# Power.net
KiCad netlist of a schematic drawn in Altium Designer
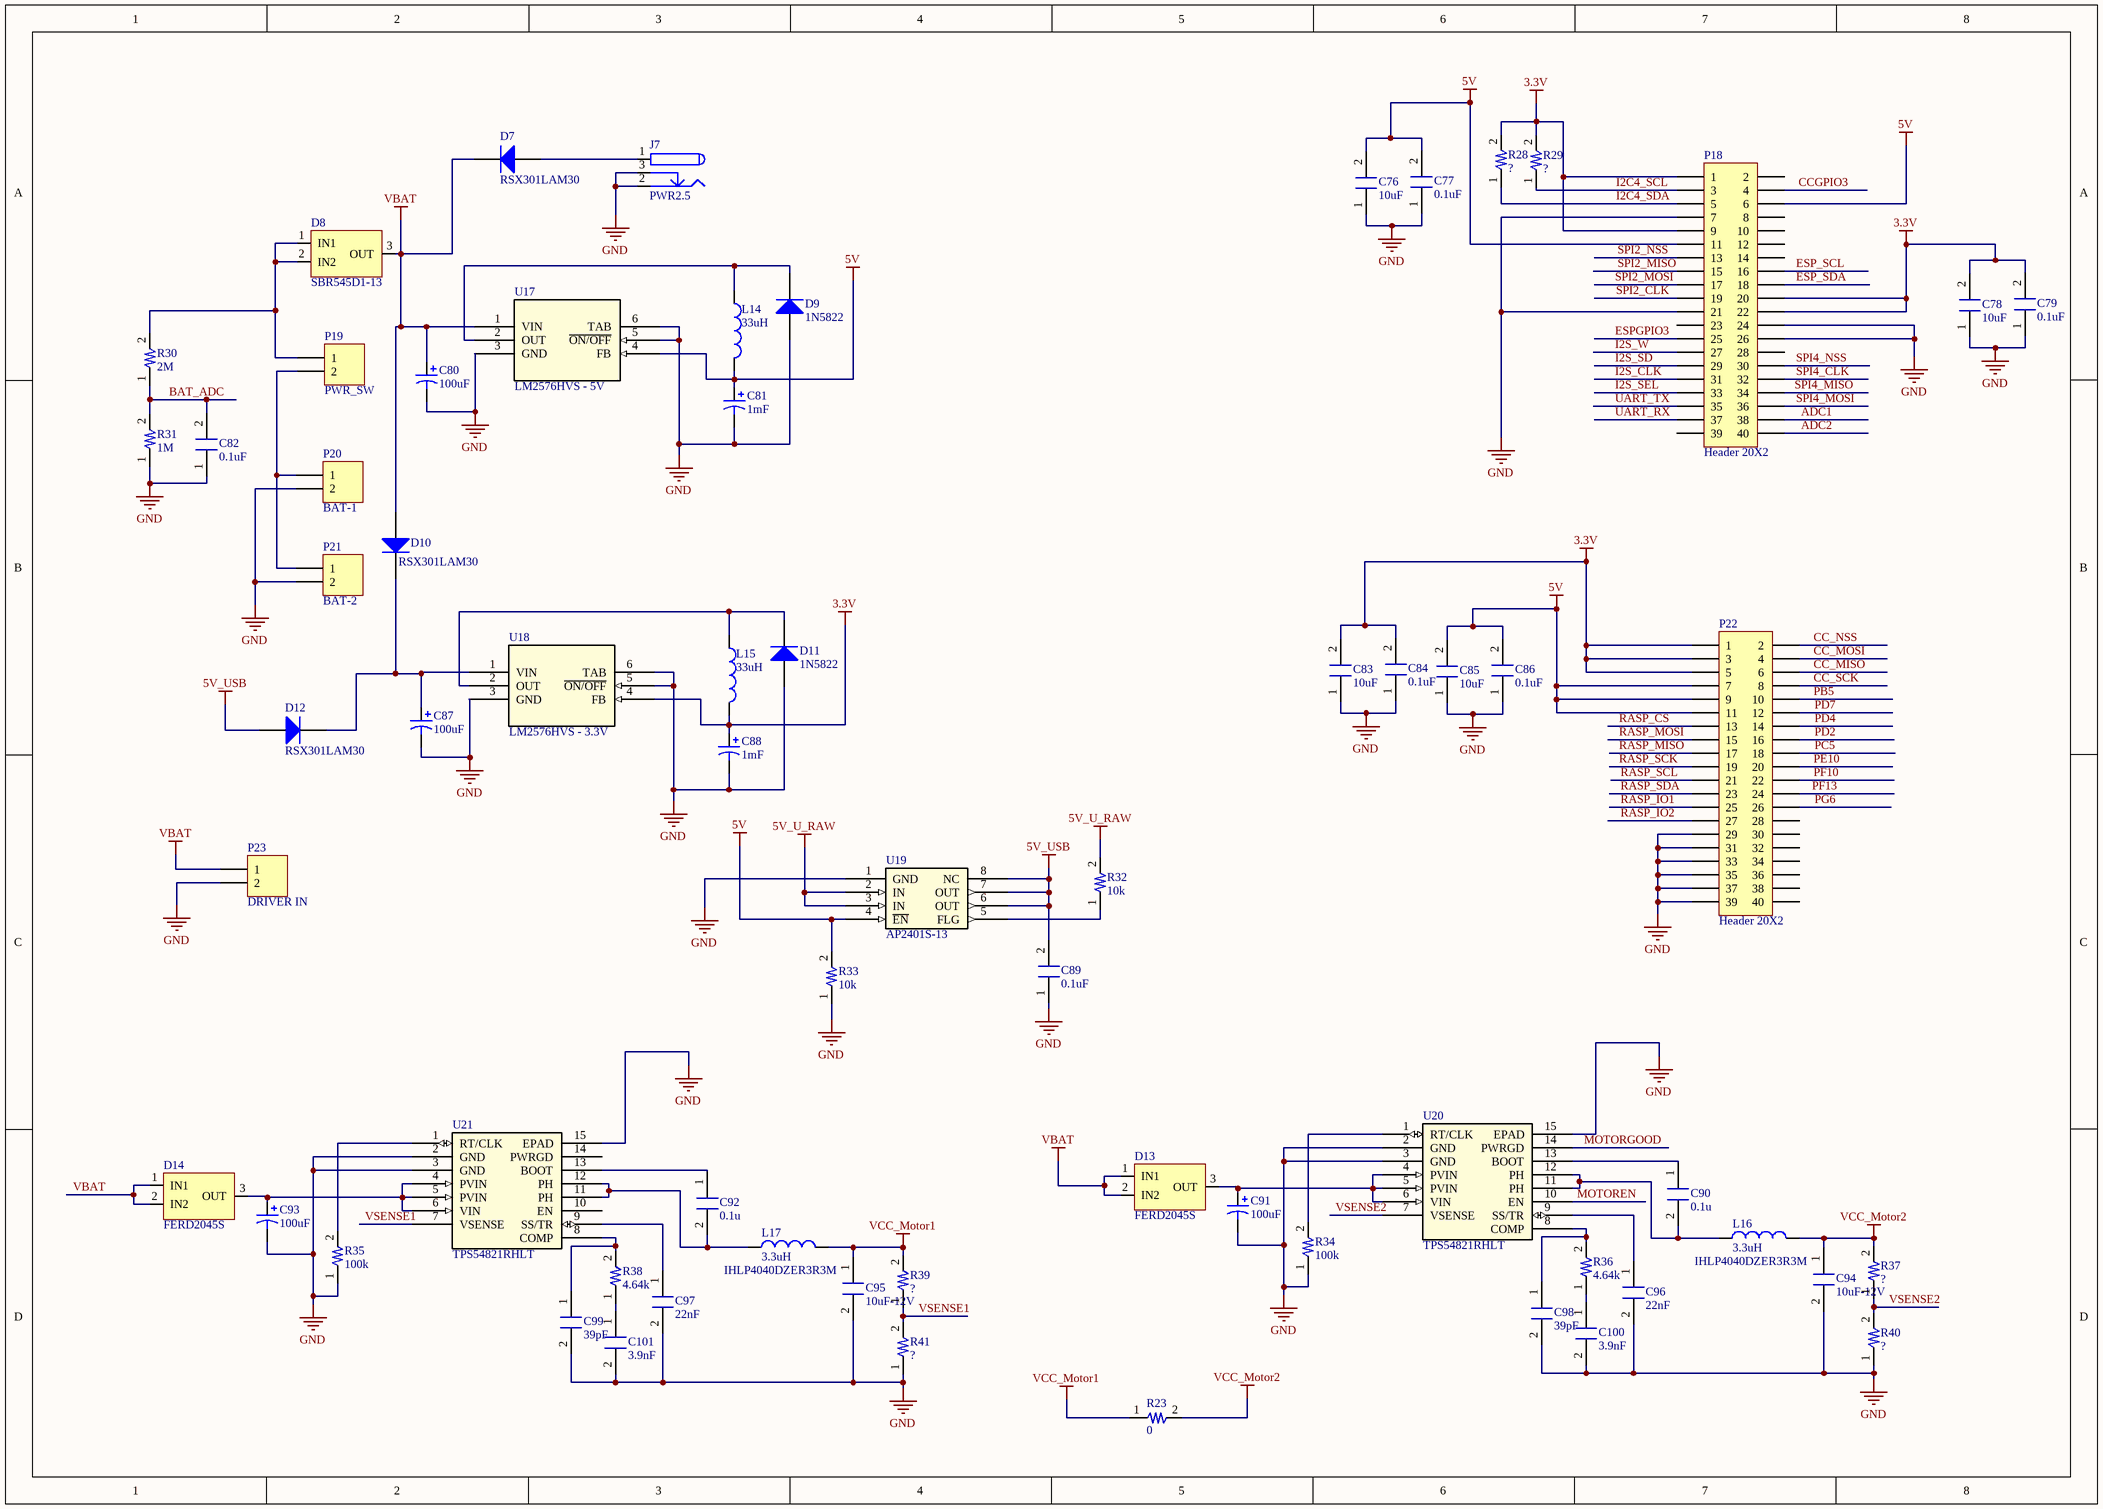
[diagram p0: Power.SchDoc]

(export (version "E")
  (design (tool "Eeschema 10.0.6"))
  (components
    (comp (ref "C76")
      (value "10uF")
      (footprint "Capacitor 0603")
      (fields (field (name "Comment") "Ceramic Capacitor"))
      (libsource (lib "Custom") (part "Ceramic Capacitor"))
    )
    (comp (ref "C77")
      (value "0.1uF")
      (footprint "Capacitor 0402")
      (fields (field (name "Comment") "Ceramic Capacitor"))
      (libsource (lib "Custom") (part "Ceramic Capacitor"))
    )
    (comp (ref "C78")
      (value "10uF")
      (footprint "Capacitor 0603")
      (fields (field (name "Comment") "Ceramic Capacitor"))
      (libsource (lib "Custom") (part "Ceramic Capacitor"))
    )
    (comp (ref "C79")
      (value "0.1uF")
      (footprint "Capacitor 0402")
      (fields (field (name "Comment") "Ceramic Capacitor"))
      (libsource (lib "Custom") (part "Ceramic Capacitor"))
    )
    (comp (ref "C80")
      (value "100uF")
      (footprint "CAPE5.0mm")
      (description "Polarized Capacitor (Radial)")
      (fields (field (name "PUBLISHER") "Altium Limited"))
      (libsource (lib "Miscellaneous Devices") (part "Cap Pol1"))
    )
    (comp (ref "C81")
      (value "1mF")
      (footprint "CAPE5.0mm")
      (description "Polarized Capacitor (Radial)")
      (fields (field (name "PUBLISHER") "Altium Limited"))
      (libsource (lib "Miscellaneous Devices") (part "Cap Pol1"))
    )
    (comp (ref "C82")
      (value "0.1uF")
      (footprint "Capacitor 0402")
      (fields (field (name "Comment") "Ceramic Capacitor"))
      (libsource (lib "Custom") (part "Ceramic Capacitor"))
    )
    (comp (ref "C83")
      (value "10uF")
      (footprint "Capacitor 0603")
      (fields (field (name "Comment") "Ceramic Capacitor"))
      (libsource (lib "Custom") (part "Ceramic Capacitor"))
    )
    (comp (ref "C84")
      (value "0.1uF")
      (footprint "Capacitor 0402")
      (fields (field (name "Comment") "Ceramic Capacitor"))
      (libsource (lib "Custom") (part "Ceramic Capacitor"))
    )
    (comp (ref "C85")
      (value "10uF")
      (footprint "Capacitor 0603")
      (fields (field (name "Comment") "Ceramic Capacitor"))
      (libsource (lib "Custom") (part "Ceramic Capacitor"))
    )
    (comp (ref "C86")
      (value "0.1uF")
      (footprint "Capacitor 0402")
      (fields (field (name "Comment") "Ceramic Capacitor"))
      (libsource (lib "Custom") (part "Ceramic Capacitor"))
    )
    (comp (ref "C87")
      (value "100uF")
      (footprint "CAPE5.0mm")
      (description "Polarized Capacitor (Radial)")
      (fields (field (name "PUBLISHER") "Altium Limited"))
      (libsource (lib "Miscellaneous Devices") (part "Cap Pol1"))
    )
    (comp (ref "C88")
      (value "1mF")
      (footprint "CAPE5.0mm")
      (description "Polarized Capacitor (Radial)")
      (fields (field (name "PUBLISHER") "Altium Limited"))
      (libsource (lib "Miscellaneous Devices") (part "Cap Pol1"))
    )
    (comp (ref "C89")
      (value "0.1uF")
      (footprint "Capacitor 0402")
      (fields (field (name "Comment") "Ceramic Capacitor"))
      (libsource (lib "Custom") (part "Ceramic Capacitor"))
    )
    (comp (ref "C90")
      (value "0.1u")
      (footprint "Capacitor 0603")
      (fields (field (name "Comment") "Ceramic Capacitor"))
      (libsource (lib "Custom") (part "Ceramic Capacitor"))
    )
    (comp (ref "C91")
      (value "100uF")
      (footprint "CAPE5.0mm")
      (description "Polarized Capacitor (Radial)")
      (fields (field (name "PUBLISHER") "Altium Limited"))
      (libsource (lib "Miscellaneous Devices") (part "Cap Pol1"))
    )
    (comp (ref "C92")
      (value "0.1u")
      (footprint "Capacitor 0603")
      (fields (field (name "Comment") "Ceramic Capacitor"))
      (libsource (lib "Custom") (part "Ceramic Capacitor"))
    )
    (comp (ref "C93")
      (value "100uF")
      (footprint "CAPE5.0mm")
      (description "Polarized Capacitor (Radial)")
      (fields (field (name "PUBLISHER") "Altium Limited"))
      (libsource (lib "Miscellaneous Devices") (part "Cap Pol1"))
    )
    (comp (ref "C94")
      (value "10uF-12V")
      (footprint "CAPAE250P680X1220_VERT")
      (fields (field (name "Comment") "Ceramic Capacitor"))
      (libsource (lib "Custom") (part "Ceramic Capacitor"))
    )
    (comp (ref "C95")
      (value "10uF-12V")
      (footprint "CAPAE250P680X1220_VERT")
      (fields (field (name "Comment") "Ceramic Capacitor"))
      (libsource (lib "Custom") (part "Ceramic Capacitor"))
    )
    (comp (ref "C96")
      (value "22nF")
      (footprint "Capacitor 0402")
      (fields (field (name "Comment") "Ceramic Capacitor"))
      (libsource (lib "Custom") (part "Ceramic Capacitor"))
    )
    (comp (ref "C97")
      (value "22nF")
      (footprint "Capacitor 0402")
      (fields (field (name "Comment") "Ceramic Capacitor"))
      (libsource (lib "Custom") (part "Ceramic Capacitor"))
    )
    (comp (ref "C98")
      (value "39pF")
      (footprint "Capacitor 0402")
      (fields (field (name "Comment") "Ceramic Capacitor"))
      (libsource (lib "Custom") (part "Ceramic Capacitor"))
    )
    (comp (ref "C99")
      (value "39pF")
      (footprint "Capacitor 0402")
      (fields (field (name "Comment") "Ceramic Capacitor"))
      (libsource (lib "Custom") (part "Ceramic Capacitor"))
    )
    (comp (ref "C100")
      (value "3.9nF")
      (footprint "Capacitor 0402")
      (fields (field (name "Comment") "Ceramic Capacitor"))
      (libsource (lib "Custom") (part "Ceramic Capacitor"))
    )
    (comp (ref "C101")
      (value "3.9nF")
      (footprint "Capacitor 0402")
      (fields (field (name "Comment") "Ceramic Capacitor"))
      (libsource (lib "Custom") (part "Ceramic Capacitor"))
    )
    (comp (ref "D7")
      (value "RSX301LAM30")
      (footprint "SOD128")
      (description "3 Amp General Purpose Rectifier")
      (fields (field (name "PUBLISHER") "Altium Limited"))
      (libsource (lib "Miscellaneous Devices") (part "Diode 1N5401"))
    )
    (comp (ref "D8")
      (value "SBR545D1-13")
      (footprint "TO-252")
      (libsource (lib "Custom") (part "Diode Array"))
    )
    (comp (ref "D9")
      (value "1N5822")
      (footprint "DO-201AD")
      (description "3 Amp General Purpose Rectifier")
      (fields (field (name "PUBLISHER") "Altium Limited"))
      (libsource (lib "Miscellaneous Devices") (part "Diode 1N5401"))
    )
    (comp (ref "D10")
      (value "RSX301LAM30")
      (footprint "SOD128")
      (description "3 Amp General Purpose Rectifier")
      (fields (field (name "PUBLISHER") "Altium Limited"))
      (libsource (lib "Miscellaneous Devices") (part "Diode 1N5401"))
    )
    (comp (ref "D11")
      (value "1N5822")
      (footprint "DO-201AD")
      (description "3 Amp General Purpose Rectifier")
      (fields (field (name "PUBLISHER") "Altium Limited"))
      (libsource (lib "Miscellaneous Devices") (part "Diode 1N5401"))
    )
    (comp (ref "D12")
      (value "RSX301LAM30")
      (footprint "SOD128")
      (description "3 Amp General Purpose Rectifier")
      (fields (field (name "PUBLISHER") "Altium Limited"))
      (libsource (lib "Miscellaneous Devices") (part "Diode 1N5401"))
    )
    (comp (ref "D13") (value "FERD2045S") (footprint "DPAK") (libsource (lib "Custom") (part "Diode Array")))
    (comp (ref "D14") (value "FERD2045S") (footprint "DPAK") (libsource (lib "Custom") (part "Diode Array")))
    (comp (ref "J7")
      (value "PWR2.5")
      (footprint "KLD-0202")
      (description "Low Voltage Power Supply Connector")
      (fields (field (name "PUBLISHER") "Altium Limited"))
      (libsource (lib "Custom") (part "PWR2.5"))
    )
    (comp (ref "L14")
      (value "33uH")
      (footprint "IND Coil")
      (description "Inductor")
      (fields (field (name "PUBLISHER") "Altium Limited"))
      (libsource (lib "Custom") (part "Inductor"))
    )
    (comp (ref "L15")
      (value "33uH")
      (footprint "IND Coil")
      (description "Inductor")
      (fields (field (name "PUBLISHER") "Altium Limited"))
      (libsource (lib "Custom") (part "Inductor"))
    )
    (comp (ref "L16")
      (value "IHLP4040DZER3R3M")
      (footprint "IND_IHLP-4040DZ-")
      (fields (field (name "ALTIUM_VALUE") "3.3uH"))
      (libsource (lib "Custom") (part "Inductor"))
    )
    (comp (ref "L17")
      (value "IHLP4040DZER3R3M")
      (footprint "IND_IHLP-4040DZ-")
      (fields (field (name "ALTIUM_VALUE") "3.3uH"))
      (libsource (lib "Custom") (part "Inductor"))
    )
    (comp (ref "P18")
      (value "Header 20X2")
      (footprint "HDR2X20")
      (description "Header, 20-Pin, Dual row")
      (fields (field (name "PUBLISHER") "Altium Limited"))
      (libsource (lib "Miscellaneous Connectors") (part "Header 20X2"))
    )
    (comp (ref "P19")
      (value "PWR_SW")
      (footprint "HDR1X2")
      (description "Header, 2-Pin")
      (fields (field (name "PUBLISHER") "Altium Limited"))
      (libsource (lib "Miscellaneous Connectors") (part "Header 2"))
    )
    (comp (ref "P20")
      (value "BAT-1")
      (footprint "BAT")
      (description "Header, 2-Pin")
      (fields (field (name "PUBLISHER") "Altium Limited"))
      (libsource (lib "Miscellaneous Connectors") (part "Header 2"))
    )
    (comp (ref "P21")
      (value "BAT-2")
      (footprint "HDR1X2")
      (description "Header, 2-Pin")
      (fields (field (name "PUBLISHER") "Altium Limited"))
      (libsource (lib "Miscellaneous Connectors") (part "Header 2"))
    )
    (comp (ref "P22")
      (value "Header 20X2")
      (footprint "HDR2X20")
      (description "Header, 20-Pin, Dual row")
      (fields (field (name "PUBLISHER") "Altium Limited"))
      (libsource (lib "Miscellaneous Connectors") (part "Header 20X2"))
    )
    (comp (ref "P23")
      (value "DRIVER IN")
      (footprint "HDR1X2")
      (description "Header, 2-Pin")
      (fields (field (name "PUBLISHER") "Altium Limited"))
      (libsource (lib "Miscellaneous Connectors") (part "Header 2"))
    )
    (comp (ref "R23")
      (value "0")
      (footprint "Resistor 0805")
      (description "General Purpose Resistor")
      (fields (field (name "Comment") "Resistor"))
      (libsource (lib "Custom") (part "Resistor"))
    )
    (comp (ref "R28")
      (value "?")
      (footprint "Resistor 0402")
      (description "General Purpose Resistor")
      (fields (field (name "Comment") "Resistor"))
      (libsource (lib "Custom") (part "Resistor"))
    )
    (comp (ref "R29")
      (value "?")
      (footprint "Resistor 0402")
      (description "General Purpose Resistor")
      (fields (field (name "Comment") "Resistor"))
      (libsource (lib "Custom") (part "Resistor"))
    )
    (comp (ref "R30")
      (value "2M")
      (footprint "Resistor 0402")
      (description "General Purpose Resistor")
      (fields (field (name "Comment") "Resistor"))
      (libsource (lib "Custom") (part "Resistor"))
    )
    (comp (ref "R31")
      (value "1M")
      (footprint "Resistor 0402")
      (description "General Purpose Resistor")
      (fields (field (name "Comment") "Resistor"))
      (libsource (lib "Custom") (part "Resistor"))
    )
    (comp (ref "R32")
      (value "10k")
      (footprint "Resistor 0402")
      (description "General Purpose Resistor")
      (fields (field (name "Comment") "Resistor"))
      (libsource (lib "Custom") (part "Resistor"))
    )
    (comp (ref "R33")
      (value "10k")
      (footprint "Resistor 0402")
      (description "General Purpose Resistor")
      (fields (field (name "Comment") "Resistor"))
      (libsource (lib "Custom") (part "Resistor"))
    )
    (comp (ref "R34")
      (value "100k")
      (footprint "Resistor 0402")
      (description "General Purpose Resistor")
      (fields (field (name "Comment") "Resistor"))
      (libsource (lib "Custom") (part "Resistor"))
    )
    (comp (ref "R35")
      (value "100k")
      (footprint "Resistor 0402")
      (description "General Purpose Resistor")
      (fields (field (name "Comment") "Resistor"))
      (libsource (lib "Custom") (part "Resistor"))
    )
    (comp (ref "R36")
      (value "4.64k")
      (footprint "Resistor 0402")
      (description "General Purpose Resistor")
      (fields (field (name "Comment") "Resistor"))
      (libsource (lib "Custom") (part "Resistor"))
    )
    (comp (ref "R37")
      (value "?")
      (footprint "Resistor 0402")
      (description "General Purpose Resistor")
      (fields (field (name "Comment") "Resistor"))
      (libsource (lib "Custom") (part "Resistor"))
    )
    (comp (ref "R38")
      (value "4.64k")
      (footprint "Resistor 0402")
      (description "General Purpose Resistor")
      (fields (field (name "Comment") "Resistor"))
      (libsource (lib "Custom") (part "Resistor"))
    )
    (comp (ref "R39")
      (value "?")
      (footprint "Resistor 0402")
      (description "General Purpose Resistor")
      (fields (field (name "Comment") "Resistor"))
      (libsource (lib "Custom") (part "Resistor"))
    )
    (comp (ref "R40")
      (value "?")
      (footprint "Resistor 0402")
      (description "General Purpose Resistor")
      (fields (field (name "Comment") "Resistor"))
      (libsource (lib "Custom") (part "Resistor"))
    )
    (comp (ref "R41")
      (value "?")
      (footprint "Resistor 0402")
      (description "General Purpose Resistor")
      (fields (field (name "Comment") "Resistor"))
      (libsource (lib "Custom") (part "Resistor"))
    )
    (comp (ref "U17")
      (value "LM2576HVS - 5V")
      (footprint "TS5B")
      (description "No Description Available")
      (libsource (lib "Custom") (part "LM2576HVS"))
    )
    (comp (ref "U18")
      (value "LM2576HVS - 3.3V")
      (footprint "TS5B")
      (description "No Description Available")
      (libsource (lib "Custom") (part "LM2576HVS"))
    )
    (comp (ref "U19")
      (value "AP2401S-13")
      (footprint "SO8")
      (description "No Description Available")
      (fields (field (name "COPYRIGHT") "Copyright (C) 2018 Accelerated Designs. All rights reserved"))
      (libsource (lib "Custom") (part "AP2401S-13"))
    )
    (comp (ref "U20")
      (value "TPS54821RHLT")
      (footprint "RHL14_2P05X2P05")
      (description "No Description Available")
      (libsource (lib "Custom") (part "TPS54821RHLT"))
    )
    (comp (ref "U21")
      (value "TPS54821RHLT")
      (footprint "RHL14_2P05X2P05")
      (description "No Description Available")
      (libsource (lib "Custom") (part "TPS54821RHLT"))
    )
  )
  (nets
    (net (code "1") (name "/ADC1") (class "Default")
      (node (ref "P18") (pin "38") (pinfunction "38_38") (pintype "passive"))
    )
    (net (code "2") (name "/ADC2") (class "Default")
      (node (ref "P18") (pin "40") (pinfunction "40_40") (pintype "passive"))
    )
    (net (code "3") (name "/BAT_ADC") (class "Default")
      (node (ref "C82") (pin "2") (pinfunction "2_2") (pintype "passive"))
      (node (ref "R30") (pin "1") (pinfunction "1_1") (pintype "passive"))
      (node (ref "R31") (pin "2") (pinfunction "2_2") (pintype "passive"))
    )
    (net (code "4") (name "/CCGPIO3") (class "Default")
      (node (ref "P18") (pin "4") (pinfunction "4_4") (pintype "passive"))
    )
    (net (code "5") (name "/CC_MISO") (class "Default")
      (node (ref "P22") (pin "6") (pinfunction "6_6") (pintype "passive"))
    )
    (net (code "6") (name "/CC_MOSI") (class "Default")
      (node (ref "P22") (pin "4") (pinfunction "4_4") (pintype "passive"))
    )
    (net (code "7") (name "/CC_NSS") (class "Default")
      (node (ref "P22") (pin "2") (pinfunction "2_2") (pintype "passive"))
    )
    (net (code "8") (name "/CC_SCK") (class "Default")
      (node (ref "P22") (pin "8") (pinfunction "8_8") (pintype "passive"))
    )
    (net (code "9") (name "/ESPGPIO3") (class "Default")
      (node (ref "P18") (pin "25") (pinfunction "25_25") (pintype "passive"))
    )
    (net (code "10") (name "/ESP_SCL") (class "Default")
      (node (ref "P18") (pin "16") (pinfunction "16_16") (pintype "passive"))
    )
    (net (code "11") (name "/ESP_SDA") (class "Default")
      (node (ref "P18") (pin "18") (pinfunction "18_18") (pintype "passive"))
    )
    (net (code "12") (name "/I2C4_SCL") (class "Default")
      (node (ref "P18") (pin "3") (pinfunction "3_3") (pintype "passive"))
      (node (ref "R29") (pin "1") (pinfunction "1_1") (pintype "passive"))
    )
    (net (code "13") (name "/I2C4_SDA") (class "Default")
      (node (ref "P18") (pin "5") (pinfunction "5_5") (pintype "passive"))
      (node (ref "R28") (pin "1") (pinfunction "1_1") (pintype "passive"))
    )
    (net (code "14") (name "/I2S_CLK") (class "Default")
      (node (ref "P18") (pin "31") (pinfunction "31_31") (pintype "passive"))
    )
    (net (code "15") (name "/I2S_SD") (class "Default")
      (node (ref "P18") (pin "29") (pinfunction "29_29") (pintype "passive"))
    )
    (net (code "16") (name "/I2S_SEL") (class "Default")
      (node (ref "P18") (pin "33") (pinfunction "33_33") (pintype "passive"))
    )
    (net (code "17") (name "/I2S_W") (class "Default")
      (node (ref "P18") (pin "27") (pinfunction "27_27") (pintype "passive"))
    )
    (net (code "18") (name "/MOTOREN") (class "Default")
      (node (ref "U20") (pin "10") (pinfunction "EN_10") (pintype "passive"))
    )
    (net (code "19") (name "/MOTORGOOD") (class "Default")
      (node (ref "U20") (pin "14") (pinfunction "PWRGD_14") (pintype "power_in"))
    )
    (net (code "20") (name "/PB5") (class "Default")
      (node (ref "P22") (pin "10") (pinfunction "10_10") (pintype "passive"))
    )
    (net (code "21") (name "/PC5") (class "Default")
      (node (ref "P22") (pin "18") (pinfunction "18_18") (pintype "passive"))
    )
    (net (code "22") (name "/PD2") (class "Default")
      (node (ref "P22") (pin "16") (pinfunction "16_16") (pintype "passive"))
    )
    (net (code "23") (name "/PD4") (class "Default")
      (node (ref "P22") (pin "14") (pinfunction "14_14") (pintype "passive"))
    )
    (net (code "24") (name "/PD7") (class "Default")
      (node (ref "P22") (pin "12") (pinfunction "12_12") (pintype "passive"))
    )
    (net (code "25") (name "/PE10") (class "Default")
      (node (ref "P22") (pin "20") (pinfunction "20_20") (pintype "passive"))
    )
    (net (code "26") (name "/PF10") (class "Default")
      (node (ref "P22") (pin "22") (pinfunction "22_22") (pintype "passive"))
    )
    (net (code "27") (name "/PF13") (class "Default")
      (node (ref "P22") (pin "24") (pinfunction "24_24") (pintype "passive"))
    )
    (net (code "28") (name "/PG6") (class "Default")
      (node (ref "P22") (pin "26") (pinfunction "26_26") (pintype "passive"))
    )
    (net (code "29") (name "/RASP_CS") (class "Default")
      (node (ref "P22") (pin "13") (pinfunction "13_13") (pintype "passive"))
    )
    (net (code "30") (name "/RASP_IO1") (class "Default")
      (node (ref "P22") (pin "25") (pinfunction "25_25") (pintype "passive"))
    )
    (net (code "31") (name "/RASP_IO2") (class "Default")
      (node (ref "P22") (pin "27") (pinfunction "27_27") (pintype "passive"))
    )
    (net (code "32") (name "/RASP_MISO") (class "Default")
      (node (ref "P22") (pin "17") (pinfunction "17_17") (pintype "passive"))
    )
    (net (code "33") (name "/RASP_MOSI") (class "Default")
      (node (ref "P22") (pin "15") (pinfunction "15_15") (pintype "passive"))
    )
    (net (code "34") (name "/RASP_SCK") (class "Default")
      (node (ref "P22") (pin "19") (pinfunction "19_19") (pintype "passive"))
    )
    (net (code "35") (name "/RASP_SCL") (class "Default")
      (node (ref "P22") (pin "21") (pinfunction "21_21") (pintype "passive"))
    )
    (net (code "36") (name "/RASP_SDA") (class "Default")
      (node (ref "P22") (pin "23") (pinfunction "23_23") (pintype "passive"))
    )
    (net (code "37") (name "/SPI2_CLK") (class "Default")
      (node (ref "P18") (pin "19") (pinfunction "19_19") (pintype "passive"))
    )
    (net (code "38") (name "/SPI2_MISO") (class "Default")
      (node (ref "P18") (pin "15") (pinfunction "15_15") (pintype "passive"))
    )
    (net (code "39") (name "/SPI2_MOSI") (class "Default")
      (node (ref "P18") (pin "17") (pinfunction "17_17") (pintype "passive"))
    )
    (net (code "40") (name "/SPI2_NSS") (class "Default")
      (node (ref "P18") (pin "13") (pinfunction "13_13") (pintype "passive"))
    )
    (net (code "41") (name "/SPI4_CLK") (class "Default")
      (node (ref "P18") (pin "32") (pinfunction "32_32") (pintype "passive"))
    )
    (net (code "42") (name "/SPI4_MISO") (class "Default")
      (node (ref "P18") (pin "34") (pinfunction "34_34") (pintype "passive"))
    )
    (net (code "43") (name "/SPI4_MOSI") (class "Default")
      (node (ref "P18") (pin "36") (pinfunction "36_36") (pintype "passive"))
    )
    (net (code "44") (name "/SPI4_NSS") (class "Default")
      (node (ref "P18") (pin "30") (pinfunction "30_30") (pintype "passive"))
    )
    (net (code "45") (name "/UART_RX") (class "Default")
      (node (ref "P18") (pin "37") (pinfunction "37_37") (pintype "passive"))
    )
    (net (code "46") (name "/UART_TX") (class "Default")
      (node (ref "P18") (pin "35") (pinfunction "35_35") (pintype "passive"))
    )
    (net (code "47") (name "/VSENSE1") (class "Default")
      (node (ref "R39") (pin "1") (pinfunction "1_1") (pintype "passive"))
      (node (ref "R41") (pin "2") (pinfunction "2_2") (pintype "passive"))
      (node (ref "U21") (pin "7") (pinfunction "VSENSE_7") (pintype "power_in"))
    )
    (net (code "48") (name "/VSENSE2") (class "Default")
      (node (ref "R37") (pin "1") (pinfunction "1_1") (pintype "passive"))
      (node (ref "R40") (pin "2") (pinfunction "2_2") (pintype "passive"))
      (node (ref "U20") (pin "7") (pinfunction "VSENSE_7") (pintype "power_in"))
    )
    (net (code "49") (name "3.3V") (class "Default")
      (node (ref "C78") (pin "2") (pinfunction "2_2") (pintype "passive"))
      (node (ref "C79") (pin "2") (pinfunction "2_2") (pintype "passive"))
      (node (ref "C83") (pin "2") (pinfunction "2_2") (pintype "passive"))
      (node (ref "C84") (pin "2") (pinfunction "2_2") (pintype "passive"))
      (node (ref "C88") (pin "1") (pinfunction "1_1") (pintype "passive"))
      (node (ref "L15") (pin "2") (pinfunction "2_2") (pintype "passive"))
      (node (ref "P18") (pin "1") (pinfunction "1_1") (pintype "passive"))
      (node (ref "P18") (pin "20") (pinfunction "20_20") (pintype "passive"))
      (node (ref "P18") (pin "22") (pinfunction "22_22") (pintype "passive"))
      (node (ref "P18") (pin "9") (pinfunction "9_9") (pintype "passive"))
      (node (ref "P22") (pin "1") (pinfunction "1_1") (pintype "passive"))
      (node (ref "P22") (pin "3") (pinfunction "3_3") (pintype "passive"))
      (node (ref "P22") (pin "5") (pinfunction "5_5") (pintype "passive"))
      (node (ref "R28") (pin "2") (pinfunction "2_2") (pintype "passive"))
      (node (ref "R29") (pin "2") (pinfunction "2_2") (pintype "passive"))
      (node (ref "U18") (pin "4") (pinfunction "FB_4") (pintype "input"))
    )
    (net (code "50") (name "5V") (class "Default")
      (node (ref "C76") (pin "2") (pinfunction "2_2") (pintype "passive"))
      (node (ref "C77") (pin "2") (pinfunction "2_2") (pintype "passive"))
      (node (ref "C81") (pin "1") (pinfunction "1_1") (pintype "passive"))
      (node (ref "C85") (pin "2") (pinfunction "2_2") (pintype "passive"))
      (node (ref "C86") (pin "2") (pinfunction "2_2") (pintype "passive"))
      (node (ref "L14") (pin "2") (pinfunction "2_2") (pintype "passive"))
      (node (ref "P18") (pin "11") (pinfunction "11_11") (pintype "passive"))
      (node (ref "P18") (pin "6") (pinfunction "6_6") (pintype "passive"))
      (node (ref "P22") (pin "11") (pinfunction "11_11") (pintype "passive"))
      (node (ref "P22") (pin "7") (pinfunction "7_7") (pintype "passive"))
      (node (ref "P22") (pin "9") (pinfunction "9_9") (pintype "passive"))
      (node (ref "R33") (pin "2") (pinfunction "2_2") (pintype "passive"))
      (node (ref "U17") (pin "4") (pinfunction "FB_4") (pintype "input"))
      (node (ref "U19") (pin "4") (pinfunction "~{EN}_4") (pintype "input"))
    )
    (net (code "51") (name "5V_USB") (class "Default")
      (node (ref "C89") (pin "2") (pinfunction "2_2") (pintype "passive"))
      (node (ref "D12") (pin "1") (pinfunction "A_1") (pintype "passive"))
      (node (ref "U19") (pin "6") (pinfunction "OUT_6") (pintype "output"))
      (node (ref "U19") (pin "7") (pinfunction "OUT_7") (pintype "output"))
      (node (ref "U19") (pin "8") (pinfunction "NC_8") (pintype "passive"))
    )
    (net (code "52") (name "5V_U_RAW") (class "Default")
      (node (ref "R32") (pin "2") (pinfunction "2_2") (pintype "passive"))
      (node (ref "U19") (pin "2") (pinfunction "IN_2") (pintype "input"))
      (node (ref "U19") (pin "3") (pinfunction "IN_3") (pintype "input"))
    )
    (net (code "53") (name "GND") (class "Default")
      (node (ref "C100") (pin "2") (pinfunction "2_2") (pintype "passive"))
      (node (ref "C101") (pin "2") (pinfunction "2_2") (pintype "passive"))
      (node (ref "C76") (pin "1") (pinfunction "1_1") (pintype "passive"))
      (node (ref "C77") (pin "1") (pinfunction "1_1") (pintype "passive"))
      (node (ref "C78") (pin "1") (pinfunction "1_1") (pintype "passive"))
      (node (ref "C79") (pin "1") (pinfunction "1_1") (pintype "passive"))
      (node (ref "C80") (pin "2") (pinfunction "2_2") (pintype "passive"))
      (node (ref "C81") (pin "2") (pinfunction "2_2") (pintype "passive"))
      (node (ref "C82") (pin "1") (pinfunction "1_1") (pintype "passive"))
      (node (ref "C83") (pin "1") (pinfunction "1_1") (pintype "passive"))
      (node (ref "C84") (pin "1") (pinfunction "1_1") (pintype "passive"))
      (node (ref "C85") (pin "1") (pinfunction "1_1") (pintype "passive"))
      (node (ref "C86") (pin "1") (pinfunction "1_1") (pintype "passive"))
      (node (ref "C87") (pin "2") (pinfunction "2_2") (pintype "passive"))
      (node (ref "C88") (pin "2") (pinfunction "2_2") (pintype "passive"))
      (node (ref "C89") (pin "1") (pinfunction "1_1") (pintype "passive"))
      (node (ref "C91") (pin "2") (pinfunction "2_2") (pintype "passive"))
      (node (ref "C93") (pin "2") (pinfunction "2_2") (pintype "passive"))
      (node (ref "C94") (pin "2") (pinfunction "2_2") (pintype "passive"))
      (node (ref "C95") (pin "2") (pinfunction "2_2") (pintype "passive"))
      (node (ref "C96") (pin "2") (pinfunction "2_2") (pintype "passive"))
      (node (ref "C97") (pin "2") (pinfunction "2_2") (pintype "passive"))
      (node (ref "C98") (pin "2") (pinfunction "2_2") (pintype "passive"))
      (node (ref "C99") (pin "2") (pinfunction "2_2") (pintype "passive"))
      (node (ref "D11") (pin "1") (pinfunction "A_1") (pintype "passive"))
      (node (ref "D9") (pin "1") (pinfunction "A_1") (pintype "passive"))
      (node (ref "J7") (pin "2") (pinfunction "2_2") (pintype "power_in"))
      (node (ref "J7") (pin "3") (pinfunction "3_3") (pintype "power_in"))
      (node (ref "P18") (pin "21") (pinfunction "21_21") (pintype "passive"))
      (node (ref "P18") (pin "24") (pinfunction "24_24") (pintype "passive"))
      (node (ref "P18") (pin "26") (pinfunction "26_26") (pintype "passive"))
      (node (ref "P18") (pin "7") (pinfunction "7_7") (pintype "passive"))
      (node (ref "P20") (pin "2") (pinfunction "2_2") (pintype "passive"))
      (node (ref "P21") (pin "2") (pinfunction "2_2") (pintype "passive"))
      (node (ref "P22") (pin "29") (pinfunction "29_29") (pintype "passive"))
      (node (ref "P22") (pin "31") (pinfunction "31_31") (pintype "passive"))
      (node (ref "P22") (pin "33") (pinfunction "33_33") (pintype "passive"))
      (node (ref "P22") (pin "35") (pinfunction "35_35") (pintype "passive"))
      (node (ref "P22") (pin "37") (pinfunction "37_37") (pintype "passive"))
      (node (ref "P22") (pin "39") (pinfunction "39_39") (pintype "passive"))
      (node (ref "P23") (pin "2") (pinfunction "2_2") (pintype "passive"))
      (node (ref "R31") (pin "1") (pinfunction "1_1") (pintype "passive"))
      (node (ref "R33") (pin "1") (pinfunction "1_1") (pintype "passive"))
      (node (ref "R34") (pin "1") (pinfunction "1_1") (pintype "passive"))
      (node (ref "R35") (pin "1") (pinfunction "1_1") (pintype "passive"))
      (node (ref "R40") (pin "1") (pinfunction "1_1") (pintype "passive"))
      (node (ref "R41") (pin "1") (pinfunction "1_1") (pintype "passive"))
      (node (ref "U17") (pin "3") (pinfunction "GND_3") (pintype "power_in"))
      (node (ref "U17") (pin "5") (pinfunction "~{ON/OFF}_5") (pintype "input"))
      (node (ref "U17") (pin "6") (pinfunction "TAB_6") (pintype "power_in"))
      (node (ref "U18") (pin "3") (pinfunction "GND_3") (pintype "power_in"))
      (node (ref "U18") (pin "5") (pinfunction "~{ON/OFF}_5") (pintype "input"))
      (node (ref "U18") (pin "6") (pinfunction "TAB_6") (pintype "power_in"))
      (node (ref "U19") (pin "1") (pinfunction "GND_1") (pintype "power_in"))
      (node (ref "U20") (pin "15") (pinfunction "EPAD_15") (pintype "passive"))
      (node (ref "U20") (pin "2") (pinfunction "GND_2") (pintype "power_in"))
      (node (ref "U20") (pin "3") (pinfunction "GND_3") (pintype "power_in"))
      (node (ref "U21") (pin "15") (pinfunction "EPAD_15") (pintype "passive"))
      (node (ref "U21") (pin "2") (pinfunction "GND_2") (pintype "power_in"))
      (node (ref "U21") (pin "3") (pinfunction "GND_3") (pintype "power_in"))
    )
    (net (code "54") (name "Net-(C90-Pad2)") (class "Default")
      (node (ref "C90") (pin "2") (pinfunction "2_2") (pintype "passive"))
      (node (ref "L16") (pin "1") (pinfunction "1_1") (pintype "passive"))
      (node (ref "U20") (pin "11") (pinfunction "PH_11") (pintype "passive"))
      (node (ref "U20") (pin "12") (pinfunction "PH_12") (pintype "passive"))
    )
    (net (code "55") (name "Net-(C92-Pad2)") (class "Default")
      (node (ref "C92") (pin "2") (pinfunction "2_2") (pintype "passive"))
      (node (ref "L17") (pin "1") (pinfunction "1_1") (pintype "passive"))
      (node (ref "U21") (pin "11") (pinfunction "PH_11") (pintype "passive"))
      (node (ref "U21") (pin "12") (pinfunction "PH_12") (pintype "passive"))
    )
    (net (code "56") (name "Net-(C100-Pad1)") (class "Default")
      (node (ref "C100") (pin "1") (pinfunction "1_1") (pintype "passive"))
      (node (ref "R36") (pin "1") (pinfunction "1_1") (pintype "passive"))
    )
    (net (code "57") (name "Net-(C101-Pad1)") (class "Default")
      (node (ref "C101") (pin "1") (pinfunction "1_1") (pintype "passive"))
      (node (ref "R38") (pin "1") (pinfunction "1_1") (pintype "passive"))
    )
    (net (code "58") (name "Net-(D7-A)") (class "Default")
      (node (ref "D7") (pin "1") (pinfunction "A_1") (pintype "passive"))
      (node (ref "J7") (pin "1") (pinfunction "1_1") (pintype "power_in"))
    )
    (net (code "59") (name "Net-(D8-IN1)") (class "Default")
      (node (ref "D8") (pin "1") (pinfunction "IN1_1") (pintype "passive"))
      (node (ref "D8") (pin "2") (pinfunction "IN2_2") (pintype "passive"))
      (node (ref "P19") (pin "1") (pinfunction "1_1") (pintype "passive"))
      (node (ref "R30") (pin "2") (pinfunction "2_2") (pintype "passive"))
    )
    (net (code "60") (name "Net-(D9-K)") (class "Default")
      (node (ref "D9") (pin "2") (pinfunction "K_2") (pintype "passive"))
      (node (ref "L14") (pin "1") (pinfunction "1_1") (pintype "passive"))
      (node (ref "U17") (pin "2") (pinfunction "OUT_2") (pintype "power_in"))
    )
    (net (code "61") (name "Net-(D10-K)") (class "Default")
      (node (ref "C87") (pin "1") (pinfunction "1_1") (pintype "passive"))
      (node (ref "D10") (pin "2") (pinfunction "K_2") (pintype "passive"))
      (node (ref "D12") (pin "2") (pinfunction "K_2") (pintype "passive"))
      (node (ref "U18") (pin "1") (pinfunction "VIN_1") (pintype "power_in"))
    )
    (net (code "62") (name "Net-(D11-K)") (class "Default")
      (node (ref "D11") (pin "2") (pinfunction "K_2") (pintype "passive"))
      (node (ref "L15") (pin "1") (pinfunction "1_1") (pintype "passive"))
      (node (ref "U18") (pin "2") (pinfunction "OUT_2") (pintype "power_in"))
    )
    (net (code "63") (name "Net-(D13-OUT)") (class "Default")
      (node (ref "C91") (pin "1") (pinfunction "1_1") (pintype "passive"))
      (node (ref "D13") (pin "3") (pinfunction "OUT_3") (pintype "passive"))
      (node (ref "U20") (pin "4") (pinfunction "PVIN_4") (pintype "input"))
      (node (ref "U20") (pin "5") (pinfunction "PVIN_5") (pintype "input"))
      (node (ref "U20") (pin "6") (pinfunction "VIN_6") (pintype "input"))
    )
    (net (code "64") (name "Net-(D14-OUT)") (class "Default")
      (node (ref "C93") (pin "1") (pinfunction "1_1") (pintype "passive"))
      (node (ref "D14") (pin "3") (pinfunction "OUT_3") (pintype "passive"))
      (node (ref "U21") (pin "4") (pinfunction "PVIN_4") (pintype "input"))
      (node (ref "U21") (pin "5") (pinfunction "PVIN_5") (pintype "input"))
      (node (ref "U21") (pin "6") (pinfunction "VIN_6") (pintype "input"))
    )
    (net (code "65") (name "Net-(P19-Pad2)") (class "Default")
      (node (ref "P19") (pin "2") (pinfunction "2_2") (pintype "passive"))
      (node (ref "P20") (pin "1") (pinfunction "1_1") (pintype "passive"))
      (node (ref "P21") (pin "1") (pinfunction "1_1") (pintype "passive"))
    )
    (net (code "66") (name "Net-(U19-FLG)") (class "Default")
      (node (ref "R32") (pin "1") (pinfunction "1_1") (pintype "passive"))
      (node (ref "U19") (pin "5") (pinfunction "FLG_5") (pintype "output"))
    )
    (net (code "67") (name "Net-(U20-BOOT)") (class "Default")
      (node (ref "C90") (pin "1") (pinfunction "1_1") (pintype "passive"))
      (node (ref "U20") (pin "13") (pinfunction "BOOT_13") (pintype "passive"))
    )
    (net (code "68") (name "Net-(U20-COMP)") (class "Default")
      (node (ref "C98") (pin "1") (pinfunction "1_1") (pintype "passive"))
      (node (ref "R36") (pin "2") (pinfunction "2_2") (pintype "passive"))
      (node (ref "U20") (pin "8") (pinfunction "COMP_8") (pintype "passive"))
    )
    (net (code "69") (name "Net-(U20-RT{slash}CLK)") (class "Default")
      (node (ref "R34") (pin "2") (pinfunction "2_2") (pintype "passive"))
      (node (ref "U20") (pin "1") (pinfunction "RT/CLK_1") (pintype "bidirectional"))
    )
    (net (code "70") (name "Net-(U20-SS{slash}TR)") (class "Default")
      (node (ref "C96") (pin "1") (pinfunction "1_1") (pintype "passive"))
      (node (ref "U20") (pin "9") (pinfunction "SS/TR_9") (pintype "bidirectional"))
    )
    (net (code "71") (name "Net-(U21-BOOT)") (class "Default")
      (node (ref "C92") (pin "1") (pinfunction "1_1") (pintype "passive"))
      (node (ref "U21") (pin "13") (pinfunction "BOOT_13") (pintype "passive"))
    )
    (net (code "72") (name "Net-(U21-COMP)") (class "Default")
      (node (ref "C99") (pin "1") (pinfunction "1_1") (pintype "passive"))
      (node (ref "R38") (pin "2") (pinfunction "2_2") (pintype "passive"))
      (node (ref "U21") (pin "8") (pinfunction "COMP_8") (pintype "passive"))
    )
    (net (code "73") (name "Net-(U21-RT{slash}CLK)") (class "Default")
      (node (ref "R35") (pin "2") (pinfunction "2_2") (pintype "passive"))
      (node (ref "U21") (pin "1") (pinfunction "RT/CLK_1") (pintype "bidirectional"))
    )
    (net (code "74") (name "Net-(U21-SS{slash}TR)") (class "Default")
      (node (ref "C97") (pin "1") (pinfunction "1_1") (pintype "passive"))
      (node (ref "U21") (pin "9") (pinfunction "SS/TR_9") (pintype "bidirectional"))
    )
    (net (code "75") (name "VBAT") (class "Default")
      (node (ref "C80") (pin "1") (pinfunction "1_1") (pintype "passive"))
      (node (ref "D10") (pin "1") (pinfunction "A_1") (pintype "passive"))
      (node (ref "D13") (pin "1") (pinfunction "IN1_1") (pintype "passive"))
      (node (ref "D13") (pin "2") (pinfunction "IN2_2") (pintype "passive"))
      (node (ref "D14") (pin "1") (pinfunction "IN1_1") (pintype "passive"))
      (node (ref "D14") (pin "2") (pinfunction "IN2_2") (pintype "passive"))
      (node (ref "D7") (pin "2") (pinfunction "K_2") (pintype "passive"))
      (node (ref "D8") (pin "3") (pinfunction "OUT_3") (pintype "passive"))
      (node (ref "P23") (pin "1") (pinfunction "1_1") (pintype "passive"))
      (node (ref "U17") (pin "1") (pinfunction "VIN_1") (pintype "power_in"))
    )
    (net (code "76") (name "VCC_Motor1") (class "Default")
      (node (ref "C95") (pin "1") (pinfunction "1_1") (pintype "passive"))
      (node (ref "L17") (pin "2") (pinfunction "2_2") (pintype "passive"))
      (node (ref "R23") (pin "1") (pinfunction "1_1") (pintype "passive"))
      (node (ref "R39") (pin "2") (pinfunction "2_2") (pintype "passive"))
    )
    (net (code "77") (name "VCC_Motor2") (class "Default")
      (node (ref "C94") (pin "1") (pinfunction "1_1") (pintype "passive"))
      (node (ref "L16") (pin "2") (pinfunction "2_2") (pintype "passive"))
      (node (ref "R23") (pin "2") (pinfunction "2_2") (pintype "passive"))
      (node (ref "R37") (pin "2") (pinfunction "2_2") (pintype "passive"))
    )
    (net (code "78") (name "unconnected-(P18-Pad2)") (class "Default")
      (node (ref "P18") (pin "2") (pinfunction "2_2") (pintype "passive"))
    )
    (net (code "79") (name "unconnected-(P18-Pad8)") (class "Default")
      (node (ref "P18") (pin "8") (pinfunction "8_8") (pintype "passive"))
    )
    (net (code "80") (name "unconnected-(P18-Pad10)") (class "Default")
      (node (ref "P18") (pin "10") (pinfunction "10_10") (pintype "passive"))
    )
    (net (code "81") (name "unconnected-(P18-Pad12)") (class "Default")
      (node (ref "P18") (pin "12") (pinfunction "12_12") (pintype "passive"))
    )
    (net (code "82") (name "unconnected-(P18-Pad14)") (class "Default")
      (node (ref "P18") (pin "14") (pinfunction "14_14") (pintype "passive"))
    )
    (net (code "83") (name "unconnected-(P18-Pad23)") (class "Default")
      (node (ref "P18") (pin "23") (pinfunction "23_23") (pintype "passive"))
    )
    (net (code "84") (name "unconnected-(P18-Pad28)") (class "Default")
      (node (ref "P18") (pin "28") (pinfunction "28_28") (pintype "passive"))
    )
    (net (code "85") (name "unconnected-(P18-Pad39)") (class "Default")
      (node (ref "P18") (pin "39") (pinfunction "39_39") (pintype "passive"))
    )
    (net (code "86") (name "unconnected-(P22-Pad28)") (class "Default")
      (node (ref "P22") (pin "28") (pinfunction "28_28") (pintype "passive"))
    )
    (net (code "87") (name "unconnected-(P22-Pad30)") (class "Default")
      (node (ref "P22") (pin "30") (pinfunction "30_30") (pintype "passive"))
    )
    (net (code "88") (name "unconnected-(P22-Pad32)") (class "Default")
      (node (ref "P22") (pin "32") (pinfunction "32_32") (pintype "passive"))
    )
    (net (code "89") (name "unconnected-(P22-Pad34)") (class "Default")
      (node (ref "P22") (pin "34") (pinfunction "34_34") (pintype "passive"))
    )
    (net (code "90") (name "unconnected-(P22-Pad36)") (class "Default")
      (node (ref "P22") (pin "36") (pinfunction "36_36") (pintype "passive"))
    )
    (net (code "91") (name "unconnected-(P22-Pad38)") (class "Default")
      (node (ref "P22") (pin "38") (pinfunction "38_38") (pintype "passive"))
    )
    (net (code "92") (name "unconnected-(P22-Pad40)") (class "Default")
      (node (ref "P22") (pin "40") (pinfunction "40_40") (pintype "passive"))
    )
    (net (code "93") (name "unconnected-(U21-EN-Pad10)") (class "Default")
      (node (ref "U21") (pin "10") (pinfunction "EN_10") (pintype "passive"))
    )
    (net (code "94") (name "unconnected-(U21-PWRGD-Pad14)") (class "Default")
      (node (ref "U21") (pin "14") (pinfunction "PWRGD_14") (pintype "power_in"))
    )
  )
)
